# Sheet1.net
KiCad netlist of a schematic drawn in Altium Designer
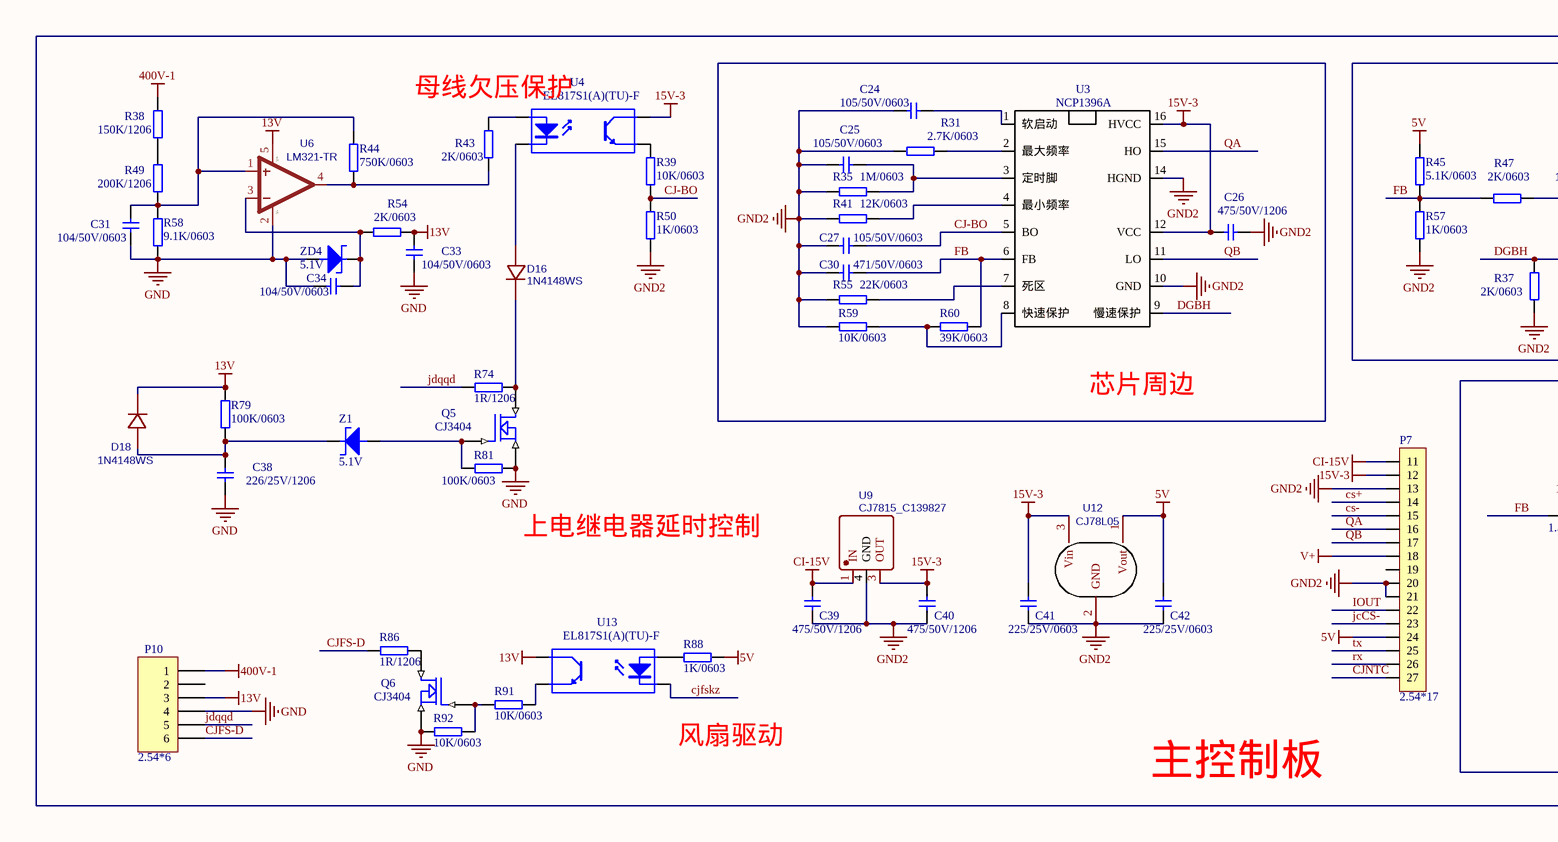
[diagram p0: Sheet1.SchDoc, left]
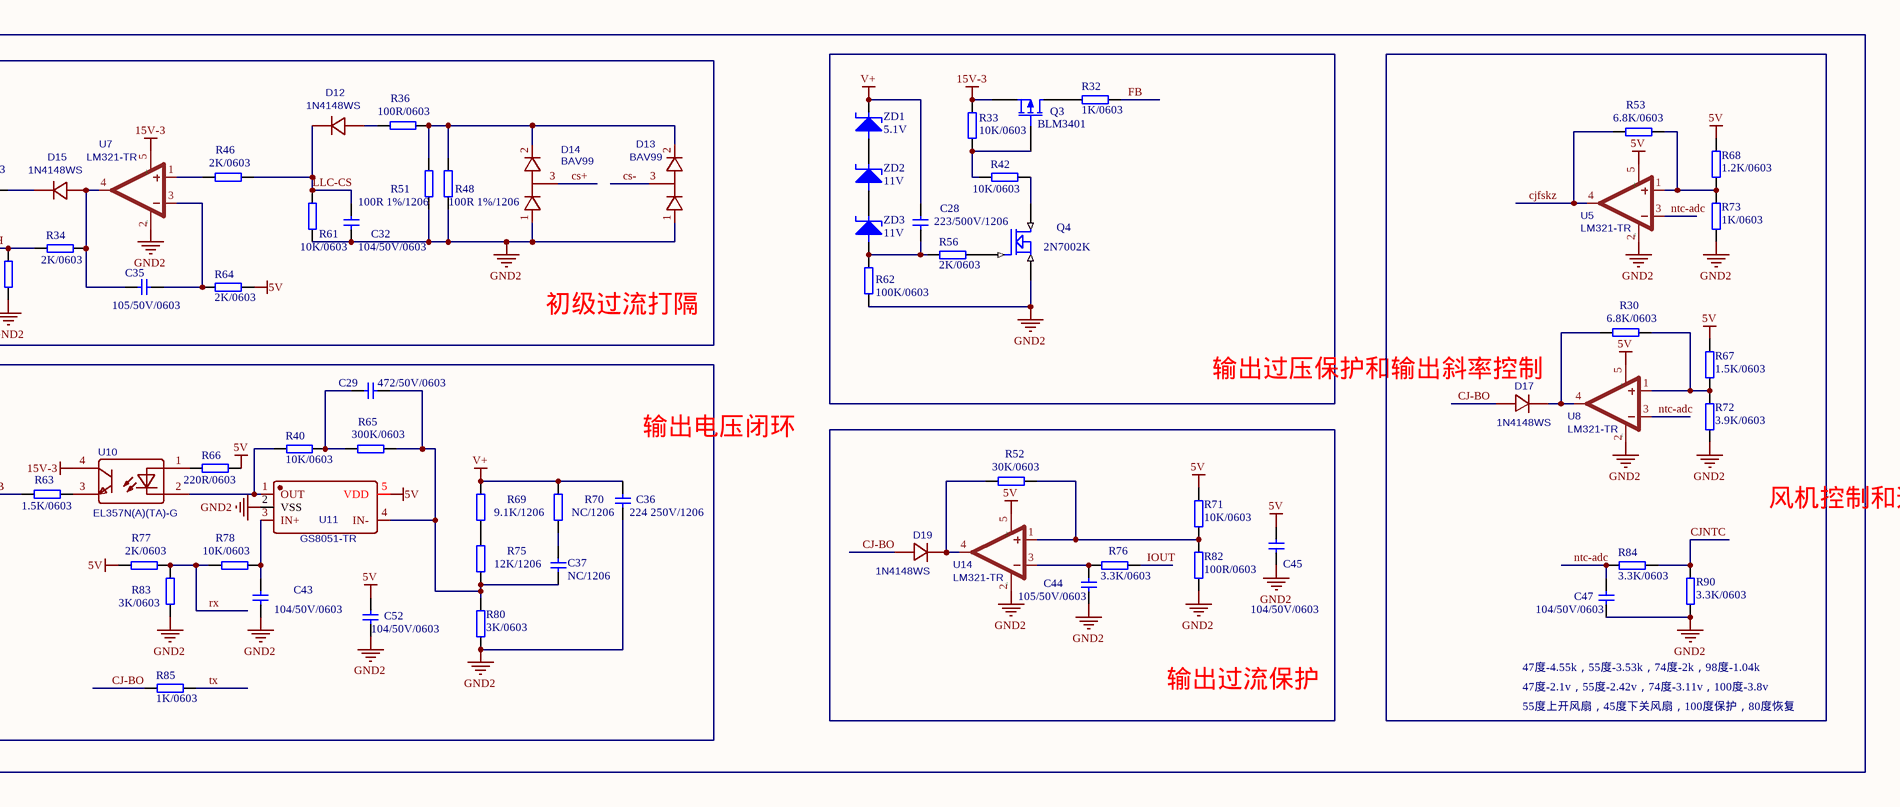
[diagram p1: Sheet1.SchDoc, right]

(export (version "E")
  (design (tool "Eeschema 10.0.6"))
  (components
    (comp (ref "C24")
      (value "105/50V/0603")
      (footprint "0603")
      (description "Capacitor")
      (libsource (lib "*") (part "CAP"))
    )
    (comp (ref "C25")
      (value "105/50V/0603")
      (footprint "0603")
      (description "Capacitor")
      (libsource (lib "*") (part "CAP"))
    )
    (comp (ref "C26")
      (value "475/50V/1206")
      (footprint "1206")
      (description "Capacitor")
      (libsource (lib "*") (part "CAP"))
    )
    (comp (ref "C27")
      (value "105/50V/0603")
      (footprint "0603")
      (description "Capacitor")
      (libsource (lib "*") (part "CAP"))
    )
    (comp (ref "C28")
      (value "223/500V/1206")
      (footprint "1206")
      (description "Capacitor")
      (libsource (lib "*") (part "CAP"))
    )
    (comp (ref "C29")
      (value "472/50V/0603")
      (footprint "0603")
      (description "Capacitor")
      (libsource (lib "") (part "CAP_1"))
    )
    (comp (ref "C30")
      (value "471/50V/0603")
      (footprint "0603")
      (description "Capacitor")
      (libsource (lib "*") (part "CAP"))
    )
    (comp (ref "C31")
      (value "104/50V/0603")
      (footprint "0603")
      (description "Capacitor")
      (libsource (lib "*") (part "CAP"))
    )
    (comp (ref "C32")
      (value "104/50V/0603")
      (footprint "0603")
      (description "Capacitor")
      (libsource (lib "*") (part "CAP"))
    )
    (comp (ref "C33")
      (value "104/50V/0603")
      (footprint "0603")
      (description "Capacitor")
      (libsource (lib "*") (part "CAP"))
    )
    (comp (ref "C34")
      (value "104/50V/0603")
      (footprint "0603")
      (description "Capacitor")
      (libsource (lib "") (part "CAP_1"))
    )
    (comp (ref "C35")
      (value "105/50V/0603")
      (footprint "0603")
      (description "Capacitor")
      (libsource (lib "") (part "CAP_1"))
    )
    (comp (ref "C36")
      (value "224 250V/1206")
      (footprint "1206")
      (description "Capacitor")
      (libsource (lib "*") (part "CAP"))
    )
    (comp (ref "C37")
      (value "NC/1206")
      (footprint "1206")
      (description "Capacitor")
      (libsource (lib "*") (part "CAP"))
    )
    (comp (ref "C38")
      (value "226/25V/1206")
      (footprint "1206")
      (description "Capacitor")
      (libsource (lib "*") (part "CAP"))
    )
    (comp (ref "C39")
      (value "475/50V/1206")
      (footprint "1206")
      (description "Capacitor")
      (libsource (lib "*") (part "CAP"))
    )
    (comp (ref "C40")
      (value "475/50V/1206")
      (footprint "1206")
      (description "Capacitor")
      (libsource (lib "*") (part "CAP"))
    )
    (comp (ref "C41")
      (value "225/25V/0603")
      (footprint "0603")
      (description "Capacitor")
      (libsource (lib "*") (part "CAP"))
    )
    (comp (ref "C42")
      (value "225/25V/0603")
      (footprint "0603")
      (description "Capacitor")
      (libsource (lib "*") (part "CAP"))
    )
    (comp (ref "C43")
      (value "104/50V/0603")
      (footprint "0603")
      (description "Capacitor")
      (libsource (lib "*") (part "CAP"))
    )
    (comp (ref "C44")
      (value "105/50V/0603")
      (footprint "0603")
      (description "Capacitor")
      (libsource (lib "*") (part "CAP"))
    )
    (comp (ref "C45")
      (value "104/50V/0603")
      (footprint "0603")
      (description "Capacitor")
      (libsource (lib "*") (part "CAP"))
    )
    (comp (ref "C47")
      (value "104/50V/0603")
      (footprint "0603")
      (description "Capacitor")
      (libsource (lib "*") (part "CAP"))
    )
    (comp (ref "C52")
      (value "104/50V/0603")
      (footprint "0603")
      (description "Capacitor")
      (libsource (lib "*") (part "CAP"))
    )
    (comp (ref "D12")
      (value "1N4148WS")
      (footprint "4148/323")
      (fields (field (name "BOM_SUPPLIER PART") "C99332"))
      (libsource (lib "altium-import") (part "root_0_1N4148WS-C99332_"))
    )
    (comp (ref "D13")
      (value "BAV99")
      (footprint "SOT-23/BAV99")
      (fields (field (name "BOM_SUPPLIER PART") "C109206") (field (name "CONTRIBUTOR") "LCSC"))
      (libsource (lib "altium-import") (part "root_1_mirrored_BAV99_C109206_"))
    )
    (comp (ref "D14")
      (value "BAV99")
      (footprint "SOT-23/BAV99")
      (fields (field (name "BOM_SUPPLIER PART") "C109206") (field (name "CONTRIBUTOR") "LCSC"))
      (libsource (lib "altium-import") (part "root_1_BAV99_C109206_"))
    )
    (comp (ref "D15")
      (value "1N4148WS")
      (footprint "4148/323")
      (fields (field (name "BOM_SUPPLIER PART") "C99332"))
      (libsource (lib "altium-import") (part "root_0_1N4148WS-C99332_"))
    )
    (comp (ref "D16")
      (value "1N4148WS")
      (footprint "4148/323")
      (fields (field (name "BOM_SUPPLIER PART") "C99332"))
      (libsource (lib "altium-import") (part "root_1_1N4148WS-C99332_"))
    )
    (comp (ref "D17")
      (value "1N4148WS")
      (footprint "4148/323")
      (fields (field (name "BOM_SUPPLIER PART") "C99332"))
      (libsource (lib "altium-import") (part "root_2_1N4148WS-C99332_"))
    )
    (comp (ref "D18")
      (value "1N4148WS")
      (footprint "4148/323")
      (fields (field (name "BOM_SUPPLIER PART") "C99332"))
      (libsource (lib "altium-import") (part "root_3_1N4148WS-C99332_"))
    )
    (comp (ref "D19")
      (value "1N4148WS")
      (footprint "4148/323")
      (fields (field (name "BOM_SUPPLIER PART") "C99332"))
      (libsource (lib "altium-import") (part "root_2_1N4148WS-C99332_"))
    )
    (comp (ref "P7")
      (value "2.54*17")
      (footprint "控制主板次级排针")
      (libsource (lib "Schlib1") (part "Component_2"))
    )
    (comp (ref "P10")
      (value "2.54*6")
      (footprint "控制主板-初级")
      (description "Header, 6-Pin")
      (fields (field (name "PUBLISHER") "Altium Limited"))
      (libsource (lib "Miscellaneous Connectors") (part "Header 6"))
    )
    (comp (ref "Q3")
      (value "BLM3401")
      (footprint "SOT-23/PMOS")
      (description "P-Channel MOSFET")
      (fields (field (name "PUBLISHER") "Altium Limited"))
      (libsource (lib "Miscellaneous Devices") (part "MOSFET-P"))
    )
    (comp (ref "Q4") (value "2N7002K") (footprint "SOT-23/MOS") (libsource (lib "sch123") (part "MOSFET N")))
    (comp (ref "Q5") (value "CJ3404") (footprint "SOT-23/MOS") (libsource (lib "sch123") (part "MOSFET N")))
    (comp (ref "Q6") (value "CJ3404") (footprint "SOT-23/MOS") (libsource (lib "sch123") (part "MOSFET N")))
    (comp (ref "R30") (value "6.8K/0603") (footprint "0603") (libsource (lib "sch123") (part "RES2")))
    (comp (ref "R31") (value "2.7K/0603") (footprint "0603") (libsource (lib "sch123") (part "RES2")))
    (comp (ref "R32") (value "1K/0603") (footprint "0603") (libsource (lib "sch123") (part "RES2")))
    (comp (ref "R33") (value "10K/0603") (footprint "0603") (libsource (lib "sch123") (part "RES2")))
    (comp (ref "R34") (value "2K/0603") (footprint "0603") (libsource (lib "sch123") (part "RES2")))
    (comp (ref "R35") (value "1M/0603") (footprint "0603") (libsource (lib "sch123") (part "RES2")))
    (comp (ref "R36") (value "100R/0603") (footprint "0603") (libsource (lib "sch123") (part "RES2")))
    (comp (ref "R37") (value "2K/0603") (footprint "0603") (libsource (lib "") (part "RES2_1")))
    (comp (ref "R38") (value "150K/1206") (footprint "1206") (libsource (lib "*") (part "RES2")))
    (comp (ref "R39") (value "10K/0603") (footprint "0603") (libsource (lib "sch123") (part "RES2")))
    (comp (ref "R40") (value "10K/0603") (footprint "0603") (libsource (lib "sch123") (part "RES2")))
    (comp (ref "R41") (value "12K/0603") (footprint "0603") (libsource (lib "sch123") (part "RES2")))
    (comp (ref "R42") (value "10K/0603") (footprint "0603") (libsource (lib "sch123") (part "RES2")))
    (comp (ref "R43") (value "2K/0603") (footprint "0603") (libsource (lib "sch123") (part "RES2")))
    (comp (ref "R44") (value "750K/0603") (footprint "0603") (libsource (lib "sch123") (part "RES2")))
    (comp (ref "R45") (value "5.1K/0603") (footprint "0603") (libsource (lib "") (part "RES2_1")))
    (comp (ref "R46") (value "2K/0603") (footprint "0603") (libsource (lib "sch123") (part "RES2")))
    (comp (ref "R47") (value "2K/0603") (footprint "0603") (libsource (lib "sch123") (part "RES2")))
    (comp (ref "R48") (value "100R 1%/1206") (footprint "1206") (libsource (lib "*") (part "RES2")))
    (comp (ref "R49") (value "200K/1206") (footprint "1206") (libsource (lib "*") (part "RES2")))
    (comp (ref "R50") (value "1K/0603") (footprint "0603") (libsource (lib "sch123") (part "RES2")))
    (comp (ref "R51") (value "100R 1%/1206") (footprint "1206") (libsource (lib "*") (part "RES2")))
    (comp (ref "R52") (value "30K/0603") (footprint "0603") (libsource (lib "sch123") (part "RES2")))
    (comp (ref "R53") (value "6.8K/0603") (footprint "0603") (libsource (lib "") (part "RES2_1")))
    (comp (ref "R54") (value "2K/0603") (footprint "0603") (libsource (lib "sch123") (part "RES2")))
    (comp (ref "R55") (value "22K/0603") (footprint "0603") (libsource (lib "sch123") (part "RES2")))
    (comp (ref "R56") (value "2K/0603") (footprint "0603") (libsource (lib "sch123") (part "RES2")))
    (comp (ref "R57") (value "1K/0603") (footprint "0603") (libsource (lib "") (part "RES2_1")))
    (comp (ref "R58") (value "9.1K/0603") (footprint "0603") (libsource (lib "sch123") (part "RES2")))
    (comp (ref "R59") (value "10K/0603") (footprint "0603") (libsource (lib "sch123") (part "RES2")))
    (comp (ref "R60") (value "39K/0603") (footprint "0603") (libsource (lib "sch123") (part "RES2")))
    (comp (ref "R61") (value "10K/0603") (footprint "0603") (libsource (lib "sch123") (part "RES2")))
    (comp (ref "R62") (value "100K/0603") (footprint "0603") (libsource (lib "sch123") (part "RES2")))
    (comp (ref "R63") (value "1.5K/0603") (footprint "0603") (libsource (lib "sch123") (part "RES2")))
    (comp (ref "R64") (value "2K/0603") (footprint "0603") (libsource (lib "sch123") (part "RES2")))
    (comp (ref "R65") (value "300K/0603") (footprint "0603") (libsource (lib "sch123") (part "RES2")))
    (comp (ref "R66") (value "220R/0603") (footprint "0603") (libsource (lib "sch123") (part "RES2")))
    (comp (ref "R67") (value "1.5K/0603") (footprint "0603") (libsource (lib "sch123") (part "RES2")))
    (comp (ref "R68") (value "1.2K/0603") (footprint "0603") (libsource (lib "sch123") (part "RES2")))
    (comp (ref "R69") (value "9.1K/1206") (footprint "1206") (libsource (lib "*") (part "RES2")))
    (comp (ref "R70") (value "NC/1206") (footprint "1206") (libsource (lib "*") (part "RES2")))
    (comp (ref "R71") (value "10K/0603") (footprint "0603") (libsource (lib "sch123") (part "RES2")))
    (comp (ref "R72") (value "3.9K/0603") (footprint "0603") (libsource (lib "sch123") (part "RES2")))
    (comp (ref "R73") (value "1K/0603") (footprint "0603") (libsource (lib "sch123") (part "RES2")))
    (comp (ref "R74") (value "1R/1206") (footprint "1206") (libsource (lib "*") (part "RES2")))
    (comp (ref "R75") (value "12K/1206") (footprint "1206") (libsource (lib "*") (part "RES2")))
    (comp (ref "R76") (value "3.3K/0603") (footprint "0603") (libsource (lib "") (part "RES2_1")))
    (comp (ref "R77") (value "2K/0603") (footprint "0603") (libsource (lib "sch123") (part "RES2")))
    (comp (ref "R78") (value "10K/0603") (footprint "0603") (libsource (lib "") (part "RES2_1")))
    (comp (ref "R79") (value "100K/0603") (footprint "0603") (libsource (lib "") (part "RES2_1")))
    (comp (ref "R80") (value "3K/0603") (footprint "0603") (libsource (lib "sch123") (part "RES2")))
    (comp (ref "R81") (value "100K/0603") (footprint "0603") (libsource (lib "sch123") (part "RES2")))
    (comp (ref "R82") (value "100R/0603") (footprint "0603") (libsource (lib "sch123") (part "RES2")))
    (comp (ref "R83") (value "3K/0603") (footprint "0603") (libsource (lib "sch123") (part "RES2")))
    (comp (ref "R84") (value "3.3K/0603") (footprint "0603") (libsource (lib "") (part "RES2_1")))
    (comp (ref "R85") (value "1K/0603") (footprint "0603") (libsource (lib "") (part "RES2_1")))
    (comp (ref "R86") (value "1R/1206") (footprint "1206") (libsource (lib "*") (part "RES2")))
    (comp (ref "R88") (value "1K/0603") (footprint "0603") (libsource (lib "sch123") (part "RES2")))
    (comp (ref "R90") (value "3.3K/0603") (footprint "0603") (libsource (lib "sch123") (part "RES2")))
    (comp (ref "R91") (value "10K/0603") (footprint "0603") (libsource (lib "sch123") (part "RES2")))
    (comp (ref "R92") (value "10K/0603") (footprint "0603") (libsource (lib "sch123") (part "RES2")))
    (comp (ref "U3") (value "NCP1396A") (footprint "SOP16") (libsource (lib "Schlib1") (part "Component_1")))
    (comp (ref "U4")
      (value "EL817S1(A)(TU)-F")
      (footprint "EL817A")
      (description "4-Pin Phototransistor Optocoupler")
      (fields (field (name "PUBLISHER") "Altium Limited"))
      (libsource (lib "Miscellaneous Devices") (part "Optoisolator1"))
    )
    (comp (ref "U5")
      (value "LM321-TR")
      (footprint "SOT23-5")
      (fields (field (name "BOM_SUPPLIER PART") "C97688"))
      (libsource (lib "altium-import") (part "root_0_mirrored_LM321-TR_"))
    )
    (comp (ref "U6")
      (value "LM321-TR")
      (footprint "SOT23-5")
      (fields (field (name "BOM_SUPPLIER PART") "C97688"))
      (libsource (lib "altium-import") (part "root_0_LM321-TR_"))
    )
    (comp (ref "U7")
      (value "LM321-TR")
      (footprint "SOT23-5")
      (fields (field (name "BOM_SUPPLIER PART") "C97688"))
      (libsource (lib "altium-import") (part "root_0_mirrored_LM321-TR_"))
    )
    (comp (ref "U8")
      (value "LM321-TR")
      (footprint "SOT23-5")
      (fields (field (name "BOM_SUPPLIER PART") "C97688"))
      (libsource (lib "altium-import") (part "root_0_mirrored_LM321-TR_"))
    )
    (comp (ref "U9")
      (value "CJ7815_C139827")
      (footprint "to-252")
      (fields
        (field (name "BOM_SUPPLIER PART") "C139827")
        (field (name "BOM_MANUFACTURER PART") "CJ7815")
        (field (name "CONTRIBUTOR") "LCSC")
      )
      (libsource (lib "altium-import") (part "root_0_CJ7815_C139827_"))
    )
    (comp (ref "U10")
      (value "EL357N(A)(TA)-G")
      (footprint "EL357")
      (fields (field (name "BOM_SUPPLIER PART") "C142286") (field (name "CONTRIBUTOR") "LCSC"))
      (libsource (lib "altium-import") (part "root_0_mirrored_EL357N(A)(TA)-G_"))
    )
    (comp (ref "U11")
      (value "GS8051-TR")
      (footprint "SOT23-5")
      (fields (field (name "BOM_SUPPLIER PART") "C157721") (field (name "CONTRIBUTOR") "LCSC"))
      (libsource (lib "altium-import") (part "root_0_GS8051-TR_"))
    )
    (comp (ref "U12")
      (value "CJ78L05")
      (footprint "CJ78J05")
      (fields (field (name "BOM_SUPPLIER PART") "C2079"))
      (libsource (lib "altium-import") (part "root_1_CJ78L05_"))
    )
    (comp (ref "U13")
      (value "EL817S1(A)(TU)-F")
      (footprint "EL817A")
      (description "4-Pin Phototransistor Optocoupler")
      (fields (field (name "PUBLISHER") "Altium Limited"))
      (libsource (lib "Miscellaneous Devices") (part "Optoisolator1"))
    )
    (comp (ref "U14")
      (value "LM321-TR")
      (footprint "SOT23-5")
      (fields (field (name "BOM_SUPPLIER PART") "C97688"))
      (libsource (lib "altium-import") (part "root_0_mirrored_LM321-TR_"))
    )
    (comp (ref "Z1")
      (value "5.1V")
      (footprint "SOD-123")
      (description "Diode Tunnel")
      (libsource (lib "sch123") (part "DIODE TUNNEL"))
    )
    (comp (ref "ZD1")
      (value "5.1V")
      (footprint "SOD-123")
      (description "Diode Tunnel")
      (libsource (lib "") (part "DIODE TUNNEL_1"))
    )
    (comp (ref "ZD2")
      (value "11V")
      (footprint "SOD-123")
      (description "Diode Tunnel")
      (libsource (lib "") (part "DIODE TUNNEL_1"))
    )
    (comp (ref "ZD3")
      (value "11V")
      (footprint "SOD-123")
      (description "Diode Tunnel")
      (libsource (lib "") (part "DIODE TUNNEL_1"))
    )
    (comp (ref "ZD4")
      (value "5.1V")
      (footprint "SOD-123")
      (description "Diode Tunnel")
      (libsource (lib "sch123") (part "DIODE TUNNEL"))
    )
  )
  (nets
    (net (code "1") (name "/CJ-BO") (class "Default")
      (node (ref "C27") (pin "1") (pinfunction "1_1") (pintype "passive"))
      (node (ref "D17") (pin "2") (pinfunction "A_2") (pintype "passive"))
      (node (ref "D19") (pin "2") (pinfunction "A_2") (pintype "passive"))
      (node (ref "R39") (pin "2") (pinfunction "2_2") (pintype "passive"))
      (node (ref "R50") (pin "1") (pinfunction "1_1") (pintype "passive"))
      (node (ref "R85") (pin "1") (pinfunction "1_1") (pintype "passive"))
      (node (ref "U3") (pin "5") (pinfunction "BO_5") (pintype "passive"))
    )
    (net (code "2") (name "/CJFS-D") (class "Default")
      (node (ref "P10") (pin "6") (pinfunction "6_6") (pintype "passive"))
      (node (ref "R86") (pin "1") (pinfunction "1_1") (pintype "passive"))
    )
    (net (code "3") (name "/CJNTC") (class "Default")
      (node (ref "P7") (pin "27") (pinfunction "27_27") (pintype "passive"))
      (node (ref "R84") (pin "1") (pinfunction "1_1") (pintype "passive"))
      (node (ref "R90") (pin "2") (pinfunction "2_2") (pintype "passive"))
    )
    (net (code "4") (name "/DGBH") (class "Default")
      (node (ref "R34") (pin "2") (pinfunction "2_2") (pintype "passive"))
      (node (ref "R37") (pin "2") (pinfunction "2_2") (pintype "passive"))
      (node (ref "U3") (pin "9") (pinfunction "慢速保护_9") (pintype "passive"))
    )
    (net (code "5") (name "/FB") (class "Default")
      (node (ref "C30") (pin "1") (pinfunction "1_1") (pintype "passive"))
      (node (ref "R32") (pin "1") (pinfunction "1_1") (pintype "passive"))
      (node (ref "R45") (pin "1") (pinfunction "1_1") (pintype "passive"))
      (node (ref "R47") (pin "1") (pinfunction "1_1") (pintype "passive"))
      (node (ref "R57") (pin "2") (pinfunction "2_2") (pintype "passive"))
      (node (ref "R60") (pin "1") (pinfunction "1_1") (pintype "passive"))
      (node (ref "R63") (pin "1") (pinfunction "1_1") (pintype "passive"))
      (node (ref "U3") (pin "6") (pinfunction "FB_6") (pintype "passive"))
    )
    (net (code "6") (name "/IOUT") (class "Default")
      (node (ref "P7") (pin "22") (pinfunction "22_22") (pintype "passive"))
      (node (ref "R76") (pin "1") (pinfunction "1_1") (pintype "passive"))
    )
    (net (code "7") (name "/LLC-CS") (class "Default")
      (node (ref "C32") (pin "1") (pinfunction "1_1") (pintype "passive"))
      (node (ref "D12") (pin "1") (pinfunction "C_1") (pintype "passive"))
      (node (ref "R46") (pin "2") (pinfunction "2_2") (pintype "passive"))
      (node (ref "R61") (pin "2") (pinfunction "2_2") (pintype "passive"))
    )
    (net (code "8") (name "/QA") (class "Default")
      (node (ref "P7") (pin "16") (pinfunction "16_16") (pintype "passive"))
      (node (ref "U3") (pin "15") (pinfunction "HO_15") (pintype "passive"))
    )
    (net (code "9") (name "/QB") (class "Default")
      (node (ref "P7") (pin "17") (pinfunction "17_17") (pintype "passive"))
      (node (ref "U3") (pin "11") (pinfunction "LO_11") (pintype "passive"))
    )
    (net (code "10") (name "/cjfskz") (class "Default")
      (node (ref "R53") (pin "1") (pinfunction "1_1") (pintype "passive"))
      (node (ref "U13") (pin "2") (pinfunction "K_2") (pintype "passive"))
      (node (ref "U5") (pin "4") (pinfunction "OUT_4") (pintype "passive"))
    )
    (net (code "11") (name "/cs+") (class "Default")
      (node (ref "D14") (pin "3") (pinfunction "3_3") (pintype "passive"))
      (node (ref "P7") (pin "14") (pinfunction "14_14") (pintype "passive"))
    )
    (net (code "12") (name "/cs-") (class "Default")
      (node (ref "D13") (pin "3") (pinfunction "3_3") (pintype "passive"))
      (node (ref "P7") (pin "15") (pinfunction "15_15") (pintype "passive"))
    )
    (net (code "13") (name "/jcCS-") (class "Default")
      (node (ref "P7") (pin "23") (pinfunction "23_23") (pintype "passive"))
    )
    (net (code "14") (name "/jdqqd") (class "Default")
      (node (ref "P10") (pin "5") (pinfunction "5_5") (pintype "passive"))
      (node (ref "R74") (pin "1") (pinfunction "1_1") (pintype "passive"))
    )
    (net (code "15") (name "/ntc-adc") (class "Default")
      (node (ref "C47") (pin "1") (pinfunction "1_1") (pintype "passive"))
      (node (ref "R84") (pin "2") (pinfunction "2_2") (pintype "passive"))
      (node (ref "U5") (pin "3") (pinfunction "-IN_3") (pintype "passive"))
      (node (ref "U8") (pin "3") (pinfunction "-IN_3") (pintype "passive"))
    )
    (net (code "16") (name "/rx") (class "Default")
      (node (ref "P7") (pin "26") (pinfunction "26_26") (pintype "passive"))
      (node (ref "R77") (pin "1") (pinfunction "1_1") (pintype "passive"))
      (node (ref "R78") (pin "2") (pinfunction "2_2") (pintype "passive"))
      (node (ref "R83") (pin "1") (pinfunction "1_1") (pintype "passive"))
    )
    (net (code "17") (name "/tx") (class "Default")
      (node (ref "P7") (pin "25") (pinfunction "25_25") (pintype "passive"))
      (node (ref "R85") (pin "2") (pinfunction "2_2") (pintype "passive"))
    )
    (net (code "18") (name "5V") (class "Default")
      (node (ref "C42") (pin "1") (pinfunction "1_1") (pintype "passive"))
      (node (ref "C45") (pin "1") (pinfunction "1_1") (pintype "passive"))
      (node (ref "C52") (pin "1") (pinfunction "1_1") (pintype "passive"))
      (node (ref "P7") (pin "24") (pinfunction "24_24") (pintype "passive"))
      (node (ref "R45") (pin "2") (pinfunction "2_2") (pintype "passive"))
      (node (ref "R64") (pin "2") (pinfunction "2_2") (pintype "passive"))
      (node (ref "R66") (pin "1") (pinfunction "1_1") (pintype "passive"))
      (node (ref "R67") (pin "2") (pinfunction "2_2") (pintype "passive"))
      (node (ref "R68") (pin "2") (pinfunction "2_2") (pintype "passive"))
      (node (ref "R71") (pin "2") (pinfunction "2_2") (pintype "passive"))
      (node (ref "R77") (pin "2") (pinfunction "2_2") (pintype "passive"))
      (node (ref "R88") (pin "1") (pinfunction "1_1") (pintype "passive"))
      (node (ref "U11") (pin "5") (pinfunction "VDD_5") (pintype "passive"))
      (node (ref "U12") (pin "1") (pinfunction "Vout_1") (pintype "passive"))
      (node (ref "U14") (pin "5") (pinfunction "V+_5") (pintype "passive"))
      (node (ref "U5") (pin "5") (pinfunction "V+_5") (pintype "passive"))
      (node (ref "U8") (pin "5") (pinfunction "V+_5") (pintype "passive"))
    )
    (net (code "19") (name "13V") (class "Default")
      (node (ref "C33") (pin "2") (pinfunction "2_2") (pintype "passive"))
      (node (ref "D18") (pin "1") (pinfunction "C_1") (pintype "passive"))
      (node (ref "P10") (pin "3") (pinfunction "3_3") (pintype "passive"))
      (node (ref "R54") (pin "2") (pinfunction "2_2") (pintype "passive"))
      (node (ref "R79") (pin "2") (pinfunction "2_2") (pintype "passive"))
      (node (ref "U13") (pin "4") (pinfunction "C_4") (pintype "passive"))
      (node (ref "U6") (pin "5") (pinfunction "V+_5") (pintype "passive"))
    )
    (net (code "20") (name "15V-3") (class "Default")
      (node (ref "C26") (pin "1") (pinfunction "1_1") (pintype "passive"))
      (node (ref "C40") (pin "1") (pinfunction "1_1") (pintype "passive"))
      (node (ref "C41") (pin "1") (pinfunction "1_1") (pintype "passive"))
      (node (ref "P7") (pin "12") (pinfunction "12_12") (pintype "passive"))
      (node (ref "Q3") (pin "3") (pinfunction "S_3") (pintype "passive"))
      (node (ref "R33") (pin "2") (pinfunction "2_2") (pintype "passive"))
      (node (ref "U10") (pin "4") (pinfunction "COL_4") (pintype "passive"))
      (node (ref "U12") (pin "3") (pinfunction "Vin_3") (pintype "passive"))
      (node (ref "U3") (pin "12") (pinfunction "VCC_12") (pintype "passive"))
      (node (ref "U3") (pin "16") (pinfunction "HVCC_16") (pintype "passive"))
      (node (ref "U4") (pin "4") (pinfunction "C_4") (pintype "passive"))
      (node (ref "U7") (pin "5") (pinfunction "V+_5") (pintype "passive"))
      (node (ref "U9") (pin "3") (pinfunction "OUT_3") (pintype "passive"))
    )
    (net (code "21") (name "400V-1") (class "Default")
      (node (ref "P10") (pin "1") (pinfunction "1_1") (pintype "passive"))
      (node (ref "R38") (pin "1") (pinfunction "1_1") (pintype "passive"))
    )
    (net (code "22") (name "CI-15V") (class "Default")
      (node (ref "C39") (pin "1") (pinfunction "1_1") (pintype "passive"))
      (node (ref "P7") (pin "11") (pinfunction "11_11") (pintype "passive"))
      (node (ref "U9") (pin "1") (pinfunction "IN_1") (pintype "passive"))
    )
    (net (code "23") (name "GND") (class "Default")
      (node (ref "C31") (pin "1") (pinfunction "1_1") (pintype "passive"))
      (node (ref "C33") (pin "1") (pinfunction "1_1") (pintype "passive"))
      (node (ref "C34") (pin "2") (pinfunction "2_2") (pintype "passive"))
      (node (ref "C38") (pin "2") (pinfunction "2_2") (pintype "passive"))
      (node (ref "P10") (pin "4") (pinfunction "4_4") (pintype "passive"))
      (node (ref "Q5") (pin "S") (pinfunction "S_S") (pintype "input"))
      (node (ref "Q6") (pin "S") (pinfunction "S_S") (pintype "input"))
      (node (ref "R58") (pin "2") (pinfunction "2_2") (pintype "passive"))
      (node (ref "R81") (pin "1") (pinfunction "1_1") (pintype "passive"))
      (node (ref "R92") (pin "1") (pinfunction "1_1") (pintype "passive"))
      (node (ref "U6") (pin "2") (pinfunction "V-_2") (pintype "passive"))
      (node (ref "ZD4") (pin "1") (pinfunction "A_1") (pintype "passive"))
    )
    (net (code "24") (name "GND2") (class "Default")
      (node (ref "C24") (pin "2") (pinfunction "2_2") (pintype "passive"))
      (node (ref "C25") (pin "2") (pinfunction "2_2") (pintype "passive"))
      (node (ref "C26") (pin "2") (pinfunction "2_2") (pintype "passive"))
      (node (ref "C27") (pin "2") (pinfunction "2_2") (pintype "passive"))
      (node (ref "C30") (pin "2") (pinfunction "2_2") (pintype "passive"))
      (node (ref "C32") (pin "2") (pinfunction "2_2") (pintype "passive"))
      (node (ref "C36") (pin "2") (pinfunction "2_2") (pintype "passive"))
      (node (ref "C39") (pin "2") (pinfunction "2_2") (pintype "passive"))
      (node (ref "C40") (pin "2") (pinfunction "2_2") (pintype "passive"))
      (node (ref "C41") (pin "2") (pinfunction "2_2") (pintype "passive"))
      (node (ref "C42") (pin "2") (pinfunction "2_2") (pintype "passive"))
      (node (ref "C43") (pin "2") (pinfunction "2_2") (pintype "passive"))
      (node (ref "C44") (pin "2") (pinfunction "2_2") (pintype "passive"))
      (node (ref "C45") (pin "2") (pinfunction "2_2") (pintype "passive"))
      (node (ref "C47") (pin "2") (pinfunction "2_2") (pintype "passive"))
      (node (ref "C52") (pin "2") (pinfunction "2_2") (pintype "passive"))
      (node (ref "D13") (pin "1") (pinfunction "1_1") (pintype "passive"))
      (node (ref "D14") (pin "1") (pinfunction "1_1") (pintype "passive"))
      (node (ref "P7") (pin "13") (pinfunction "13_13") (pintype "passive"))
      (node (ref "P7") (pin "20") (pinfunction "20_20") (pintype "passive"))
      (node (ref "P7") (pin "21") (pinfunction "21_21") (pintype "passive"))
      (node (ref "Q4") (pin "S") (pinfunction "S_S") (pintype "input"))
      (node (ref "R31") (pin "1") (pinfunction "1_1") (pintype "passive"))
      (node (ref "R35") (pin "1") (pinfunction "1_1") (pintype "passive"))
      (node (ref "R37") (pin "1") (pinfunction "1_1") (pintype "passive"))
      (node (ref "R41") (pin "1") (pinfunction "1_1") (pintype "passive"))
      (node (ref "R48") (pin "2") (pinfunction "2_2") (pintype "passive"))
      (node (ref "R50") (pin "2") (pinfunction "2_2") (pintype "passive"))
      (node (ref "R51") (pin "2") (pinfunction "2_2") (pintype "passive"))
      (node (ref "R55") (pin "1") (pinfunction "1_1") (pintype "passive"))
      (node (ref "R57") (pin "1") (pinfunction "1_1") (pintype "passive"))
      (node (ref "R59") (pin "2") (pinfunction "2_2") (pintype "passive"))
      (node (ref "R61") (pin "1") (pinfunction "1_1") (pintype "passive"))
      (node (ref "R62") (pin "1") (pinfunction "1_1") (pintype "passive"))
      (node (ref "R72") (pin "1") (pinfunction "1_1") (pintype "passive"))
      (node (ref "R73") (pin "1") (pinfunction "1_1") (pintype "passive"))
      (node (ref "R80") (pin "1") (pinfunction "1_1") (pintype "passive"))
      (node (ref "R82") (pin "1") (pinfunction "1_1") (pintype "passive"))
      (node (ref "R83") (pin "2") (pinfunction "2_2") (pintype "passive"))
      (node (ref "R90") (pin "1") (pinfunction "1_1") (pintype "passive"))
      (node (ref "U11") (pin "2") (pinfunction "VSS_2") (pintype "passive"))
      (node (ref "U12") (pin "2") (pinfunction "GND_2") (pintype "passive"))
      (node (ref "U14") (pin "2") (pinfunction "V-_2") (pintype "passive"))
      (node (ref "U3") (pin "10") (pinfunction "GND_10") (pintype "passive"))
      (node (ref "U3") (pin "14") (pinfunction "HGND_14") (pintype "passive"))
      (node (ref "U5") (pin "2") (pinfunction "V-_2") (pintype "passive"))
      (node (ref "U7") (pin "2") (pinfunction "V-_2") (pintype "passive"))
      (node (ref "U8") (pin "2") (pinfunction "V-_2") (pintype "passive"))
      (node (ref "U9") (pin "4") (pinfunction "GND_4") (pintype "passive"))
    )
    (net (code "25") (name "Net-(C29-Pad1)") (class "Default")
      (node (ref "C29") (pin "1") (pinfunction "1_1") (pintype "passive"))
      (node (ref "R40") (pin "1") (pinfunction "1_1") (pintype "passive"))
      (node (ref "R65") (pin "1") (pinfunction "1_1") (pintype "passive"))
    )
    (net (code "26") (name "Net-(C37-Pad1)") (class "Default")
      (node (ref "C37") (pin "1") (pinfunction "1_1") (pintype "passive"))
      (node (ref "R70") (pin "2") (pinfunction "2_2") (pintype "passive"))
    )
    (net (code "27") (name "Net-(D12-A)") (class "Default")
      (node (ref "D12") (pin "2") (pinfunction "A_2") (pintype "passive"))
      (node (ref "R36") (pin "1") (pinfunction "1_1") (pintype "passive"))
    )
    (net (code "28") (name "Net-(D13-Pad2)") (class "Default")
      (node (ref "D13") (pin "2") (pinfunction "2_2") (pintype "passive"))
      (node (ref "D14") (pin "2") (pinfunction "2_2") (pintype "passive"))
      (node (ref "R36") (pin "2") (pinfunction "2_2") (pintype "passive"))
      (node (ref "R48") (pin "1") (pinfunction "1_1") (pintype "passive"))
      (node (ref "R51") (pin "1") (pinfunction "1_1") (pintype "passive"))
    )
    (net (code "29") (name "Net-(D15-A)") (class "Default")
      (node (ref "C35") (pin "1") (pinfunction "1_1") (pintype "passive"))
      (node (ref "D15") (pin "2") (pinfunction "A_2") (pintype "passive"))
      (node (ref "R34") (pin "1") (pinfunction "1_1") (pintype "passive"))
      (node (ref "U7") (pin "4") (pinfunction "OUT_4") (pintype "passive"))
    )
    (net (code "30") (name "Net-(D15-C)") (class "Default")
      (node (ref "D15") (pin "1") (pinfunction "C_1") (pintype "passive"))
      (node (ref "R47") (pin "2") (pinfunction "2_2") (pintype "passive"))
    )
    (net (code "31") (name "Net-(D16-A)") (class "Default")
      (node (ref "D16") (pin "2") (pinfunction "A_2") (pintype "passive"))
      (node (ref "U4") (pin "2") (pinfunction "K_2") (pintype "passive"))
    )
    (net (code "32") (name "Net-(D16-C)") (class "Default")
      (node (ref "D16") (pin "1") (pinfunction "C_1") (pintype "passive"))
      (node (ref "Q5") (pin "D") (pinfunction "D_D") (pintype "input"))
      (node (ref "R74") (pin "2") (pinfunction "2_2") (pintype "passive"))
    )
    (net (code "33") (name "Net-(D17-C)") (class "Default")
      (node (ref "D17") (pin "1") (pinfunction "C_1") (pintype "passive"))
      (node (ref "R30") (pin "2") (pinfunction "2_2") (pintype "passive"))
      (node (ref "U8") (pin "4") (pinfunction "OUT_4") (pintype "passive"))
    )
    (net (code "34") (name "Net-(D18-A)") (class "Default")
      (node (ref "C38") (pin "1") (pinfunction "1_1") (pintype "passive"))
      (node (ref "D18") (pin "2") (pinfunction "A_2") (pintype "passive"))
      (node (ref "R79") (pin "1") (pinfunction "1_1") (pintype "passive"))
      (node (ref "Z1") (pin "2") (pinfunction "K_2") (pintype "passive"))
    )
    (net (code "35") (name "Net-(D19-C)") (class "Default")
      (node (ref "D19") (pin "1") (pinfunction "C_1") (pintype "passive"))
      (node (ref "R52") (pin "2") (pinfunction "2_2") (pintype "passive"))
      (node (ref "U14") (pin "4") (pinfunction "OUT_4") (pintype "passive"))
    )
    (net (code "36") (name "Net-(Q3-D)") (class "Default")
      (node (ref "Q3") (pin "1") (pinfunction "D_1") (pintype "passive"))
      (node (ref "R32") (pin "2") (pinfunction "2_2") (pintype "passive"))
    )
    (net (code "37") (name "Net-(Q3-G)") (class "Default")
      (node (ref "Q3") (pin "2") (pinfunction "G_2") (pintype "passive"))
      (node (ref "R33") (pin "1") (pinfunction "1_1") (pintype "passive"))
      (node (ref "R42") (pin "2") (pinfunction "2_2") (pintype "passive"))
    )
    (net (code "38") (name "Net-(Q4-PadD)") (class "Default")
      (node (ref "Q4") (pin "D") (pinfunction "D_D") (pintype "input"))
      (node (ref "R42") (pin "1") (pinfunction "1_1") (pintype "passive"))
    )
    (net (code "39") (name "Net-(Q4-PadG)") (class "Default")
      (node (ref "Q4") (pin "G") (pinfunction "G_G") (pintype "input"))
      (node (ref "R56") (pin "1") (pinfunction "1_1") (pintype "passive"))
    )
    (net (code "40") (name "Net-(Q6-PadD)") (class "Default")
      (node (ref "Q6") (pin "D") (pinfunction "D_D") (pintype "input"))
      (node (ref "R86") (pin "2") (pinfunction "2_2") (pintype "passive"))
    )
    (net (code "41") (name "Net-(Q6-PadG)") (class "Default")
      (node (ref "Q6") (pin "G") (pinfunction "G_G") (pintype "input"))
      (node (ref "R91") (pin "1") (pinfunction "1_1") (pintype "passive"))
      (node (ref "R92") (pin "2") (pinfunction "2_2") (pintype "passive"))
    )
    (net (code "42") (name "Net-(R38-Pad2)") (class "Default")
      (node (ref "R38") (pin "2") (pinfunction "2_2") (pintype "passive"))
      (node (ref "R49") (pin "1") (pinfunction "1_1") (pintype "passive"))
    )
    (net (code "43") (name "Net-(R69-Pad2)") (class "Default")
      (node (ref "R69") (pin "2") (pinfunction "2_2") (pintype "passive"))
      (node (ref "R75") (pin "1") (pinfunction "1_1") (pintype "passive"))
    )
    (net (code "44") (name "Net-(U3-定时脚)") (class "Default")
      (node (ref "C25") (pin "1") (pinfunction "1_1") (pintype "passive"))
      (node (ref "R35") (pin "2") (pinfunction "2_2") (pintype "passive"))
      (node (ref "U3") (pin "3") (pinfunction "定时脚_3") (pintype "passive"))
    )
    (net (code "45") (name "Net-(U3-快速保护)") (class "Default")
      (node (ref "R59") (pin "1") (pinfunction "1_1") (pintype "passive"))
      (node (ref "R60") (pin "2") (pinfunction "2_2") (pintype "passive"))
      (node (ref "U3") (pin "8") (pinfunction "快速保护_8") (pintype "passive"))
    )
    (net (code "46") (name "Net-(U3-最大频率)") (class "Default")
      (node (ref "R31") (pin "2") (pinfunction "2_2") (pintype "passive"))
      (node (ref "U3") (pin "2") (pinfunction "最大频率_2") (pintype "passive"))
    )
    (net (code "47") (name "Net-(U3-最小频率)") (class "Default")
      (node (ref "R41") (pin "2") (pinfunction "2_2") (pintype "passive"))
      (node (ref "U3") (pin "4") (pinfunction "最小频率_4") (pintype "passive"))
    )
    (net (code "48") (name "Net-(U3-死区)") (class "Default")
      (node (ref "R55") (pin "2") (pinfunction "2_2") (pintype "passive"))
      (node (ref "U3") (pin "7") (pinfunction "死区_7") (pintype "passive"))
    )
    (net (code "49") (name "Net-(U3-软启动)") (class "Default")
      (node (ref "C24") (pin "1") (pinfunction "1_1") (pintype "passive"))
      (node (ref "U3") (pin "1") (pinfunction "软启动_1") (pintype "passive"))
    )
    (net (code "50") (name "Net-(U4-A)") (class "Default")
      (node (ref "R43") (pin "1") (pinfunction "1_1") (pintype "passive"))
      (node (ref "U4") (pin "1") (pinfunction "A_1") (pintype "passive"))
    )
    (net (code "51") (name "Net-(U4-E)") (class "Default")
      (node (ref "R39") (pin "1") (pinfunction "1_1") (pintype "passive"))
      (node (ref "U4") (pin "3") (pinfunction "E_3") (pintype "passive"))
    )
    (net (code "52") (name "Net-(U5-+IN)") (class "Default")
      (node (ref "R53") (pin "2") (pinfunction "2_2") (pintype "passive"))
      (node (ref "R68") (pin "1") (pinfunction "1_1") (pintype "passive"))
      (node (ref "R73") (pin "2") (pinfunction "2_2") (pintype "passive"))
      (node (ref "U5") (pin "1") (pinfunction "+IN_1") (pintype "passive"))
    )
    (net (code "53") (name "Net-(U6-+IN)") (class "Default")
      (node (ref "C31") (pin "2") (pinfunction "2_2") (pintype "passive"))
      (node (ref "R44") (pin "2") (pinfunction "2_2") (pintype "passive"))
      (node (ref "R49") (pin "2") (pinfunction "2_2") (pintype "passive"))
      (node (ref "R58") (pin "1") (pinfunction "1_1") (pintype "passive"))
      (node (ref "U6") (pin "1") (pinfunction "+IN_1") (pintype "passive"))
    )
    (net (code "54") (name "Net-(U6--IN)") (class "Default")
      (node (ref "C34") (pin "1") (pinfunction "1_1") (pintype "passive"))
      (node (ref "R54") (pin "1") (pinfunction "1_1") (pintype "passive"))
      (node (ref "U6") (pin "3") (pinfunction "-IN_3") (pintype "passive"))
      (node (ref "ZD4") (pin "2") (pinfunction "K_2") (pintype "passive"))
    )
    (net (code "55") (name "Net-(U6-OUT)") (class "Default")
      (node (ref "R43") (pin "2") (pinfunction "2_2") (pintype "passive"))
      (node (ref "R44") (pin "1") (pinfunction "1_1") (pintype "passive"))
      (node (ref "U6") (pin "4") (pinfunction "OUT_4") (pintype "passive"))
    )
    (net (code "56") (name "Net-(U7-+IN)") (class "Default")
      (node (ref "R46") (pin "1") (pinfunction "1_1") (pintype "passive"))
      (node (ref "U7") (pin "1") (pinfunction "+IN_1") (pintype "passive"))
    )
    (net (code "57") (name "Net-(U7--IN)") (class "Default")
      (node (ref "C35") (pin "2") (pinfunction "2_2") (pintype "passive"))
      (node (ref "R64") (pin "1") (pinfunction "1_1") (pintype "passive"))
      (node (ref "U7") (pin "3") (pinfunction "-IN_3") (pintype "passive"))
    )
    (net (code "58") (name "Net-(U8-+IN)") (class "Default")
      (node (ref "R30") (pin "1") (pinfunction "1_1") (pintype "passive"))
      (node (ref "R67") (pin "1") (pinfunction "1_1") (pintype "passive"))
      (node (ref "R72") (pin "2") (pinfunction "2_2") (pintype "passive"))
      (node (ref "U8") (pin "1") (pinfunction "+IN_1") (pintype "passive"))
    )
    (net (code "59") (name "Net-(U10-AN)") (class "Default")
      (node (ref "R66") (pin "2") (pinfunction "2_2") (pintype "passive"))
      (node (ref "U10") (pin "1") (pinfunction "AN_1") (pintype "passive"))
    )
    (net (code "60") (name "Net-(U10-CA)") (class "Default")
      (node (ref "R40") (pin "2") (pinfunction "2_2") (pintype "passive"))
      (node (ref "U10") (pin "2") (pinfunction "CA_2") (pintype "passive"))
      (node (ref "U11") (pin "1") (pinfunction "OUT_1") (pintype "passive"))
    )
    (net (code "61") (name "Net-(U10-EM)") (class "Default")
      (node (ref "R63") (pin "2") (pinfunction "2_2") (pintype "passive"))
      (node (ref "U10") (pin "3") (pinfunction "EM_3") (pintype "passive"))
    )
    (net (code "62") (name "Net-(U11-IN+)") (class "Default")
      (node (ref "C43") (pin "1") (pinfunction "1_1") (pintype "passive"))
      (node (ref "R78") (pin "1") (pinfunction "1_1") (pintype "passive"))
      (node (ref "U11") (pin "3") (pinfunction "IN+_3") (pintype "passive"))
    )
    (net (code "63") (name "Net-(U11-IN-)") (class "Default")
      (node (ref "C29") (pin "2") (pinfunction "2_2") (pintype "passive"))
      (node (ref "C37") (pin "2") (pinfunction "2_2") (pintype "passive"))
      (node (ref "R65") (pin "2") (pinfunction "2_2") (pintype "passive"))
      (node (ref "R75") (pin "2") (pinfunction "2_2") (pintype "passive"))
      (node (ref "R80") (pin "2") (pinfunction "2_2") (pintype "passive"))
      (node (ref "U11") (pin "4") (pinfunction "IN-_4") (pintype "passive"))
    )
    (net (code "64") (name "Net-(U13-A)") (class "Default")
      (node (ref "R88") (pin "2") (pinfunction "2_2") (pintype "passive"))
      (node (ref "U13") (pin "1") (pinfunction "A_1") (pintype "passive"))
    )
    (net (code "65") (name "Net-(U13-E)") (class "Default")
      (node (ref "R91") (pin "2") (pinfunction "2_2") (pintype "passive"))
      (node (ref "U13") (pin "3") (pinfunction "E_3") (pintype "passive"))
    )
    (net (code "66") (name "Net-(U14-+IN)") (class "Default")
      (node (ref "R52") (pin "1") (pinfunction "1_1") (pintype "passive"))
      (node (ref "R71") (pin "1") (pinfunction "1_1") (pintype "passive"))
      (node (ref "R82") (pin "2") (pinfunction "2_2") (pintype "passive"))
      (node (ref "U14") (pin "1") (pinfunction "+IN_1") (pintype "passive"))
    )
    (net (code "67") (name "Net-(U14--IN)") (class "Default")
      (node (ref "C44") (pin "1") (pinfunction "1_1") (pintype "passive"))
      (node (ref "R76") (pin "2") (pinfunction "2_2") (pintype "passive"))
      (node (ref "U14") (pin "3") (pinfunction "-IN_3") (pintype "passive"))
    )
    (net (code "68") (name "Net-(Z1-A)") (class "Default")
      (node (ref "Q5") (pin "G") (pinfunction "G_G") (pintype "input"))
      (node (ref "R81") (pin "2") (pinfunction "2_2") (pintype "passive"))
      (node (ref "Z1") (pin "1") (pinfunction "A_1") (pintype "passive"))
    )
    (net (code "69") (name "Net-(ZD1-A)") (class "Default")
      (node (ref "ZD1") (pin "1") (pinfunction "A_1") (pintype "passive"))
      (node (ref "ZD2") (pin "2") (pinfunction "K_2") (pintype "passive"))
    )
    (net (code "70") (name "Net-(ZD2-A)") (class "Default")
      (node (ref "ZD2") (pin "1") (pinfunction "A_1") (pintype "passive"))
      (node (ref "ZD3") (pin "2") (pinfunction "K_2") (pintype "passive"))
    )
    (net (code "71") (name "Net-(ZD3-A)") (class "Default")
      (node (ref "C28") (pin "2") (pinfunction "2_2") (pintype "passive"))
      (node (ref "R56") (pin "2") (pinfunction "2_2") (pintype "passive"))
      (node (ref "R62") (pin "2") (pinfunction "2_2") (pintype "passive"))
      (node (ref "ZD3") (pin "1") (pinfunction "A_1") (pintype "passive"))
    )
    (net (code "72") (name "V+") (class "Default")
      (node (ref "C28") (pin "1") (pinfunction "1_1") (pintype "passive"))
      (node (ref "C36") (pin "1") (pinfunction "1_1") (pintype "passive"))
      (node (ref "P7") (pin "18") (pinfunction "18_18") (pintype "passive"))
      (node (ref "R69") (pin "1") (pinfunction "1_1") (pintype "passive"))
      (node (ref "R70") (pin "1") (pinfunction "1_1") (pintype "passive"))
      (node (ref "ZD1") (pin "2") (pinfunction "K_2") (pintype "passive"))
    )
    (net (code "73") (name "unconnected-(P7-Pad19)") (class "Default")
      (node (ref "P7") (pin "19") (pinfunction "19_19") (pintype "passive"))
    )
    (net (code "74") (name "unconnected-(P10-Pad2)") (class "Default")
      (node (ref "P10") (pin "2") (pinfunction "2_2") (pintype "passive"))
    )
  )
)
